# SWReg.net
KiCad netlist of a schematic drawn in Altium Designer
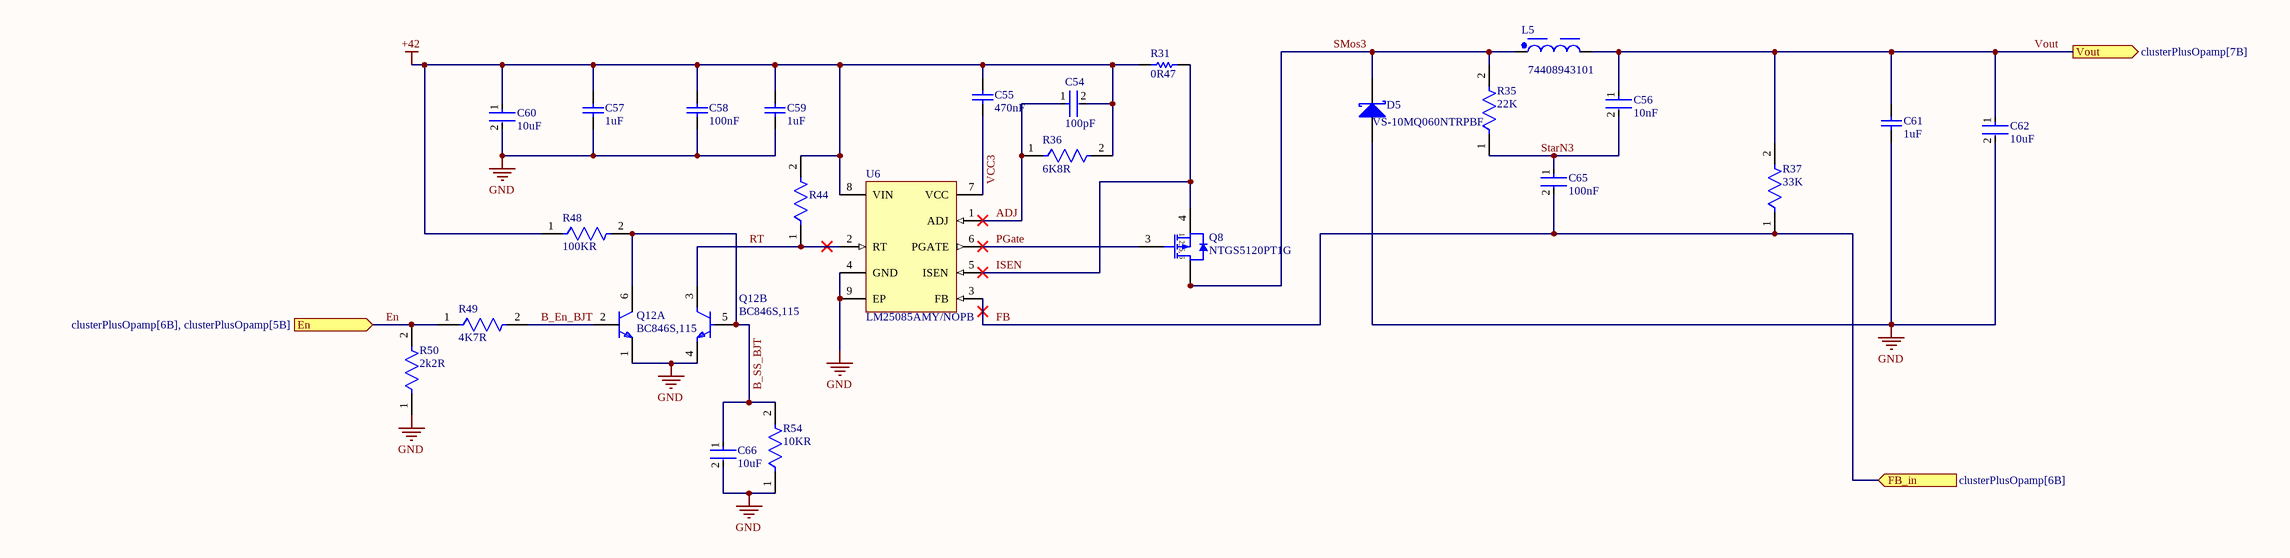
[diagram p0: SWReg.SchDoc]

(export (version "E")
  (design (tool "Eeschema 10.0.6"))
  (components
    (comp (ref "C54")
      (value "100pF")
      (footprint "FP-C0402-BB-MFG")
      (description "CAP CER 10PF 25V 5% NP0 0402")
      (fields
        (field (name "OCTOPART") "https://octopart.com/c0402c100j3gactu-kemet-9138549")
        (field (name "MANUFACTURER PART NUMBER") "C0402C100J3GACTU")
      )
      (libsource (lib "Altium Content Vault") (part "b4654b650e69147ec39a6b967a45e02"))
    )
    (comp (ref "C55")
      (value "470nF")
      (footprint "CAPC1608X90X35LL15T15")
      (fields (field (name "MANUFACTURER") "Kemet") (field (name "PART NUMBER") "C0603C105K4RACTU"))
      (libsource (lib "Altium Content Vault") (part "CAP"))
    )
    (comp (ref "C56")
      (value "10nF")
      (footprint "FP-CC1206-1_25-MFG")
      (description "CAP CER 0.1UF 50V X7R 1206")
      (fields
        (field (name "OCTOPART") "https://octopart.com/cc1206krx7r9bb104-yageo-39467816")
        (field (name "TOLERANCE") "0.1")
      )
      (libsource (lib "Altium Content Vault") (part "11868f565c42a9108669ba33697ecf6"))
    )
    (comp (ref "C57")
      (value "1uF")
      (footprint "CAPC1608X90X35LL15T15")
      (fields (field (name "MANUFACTURER") "Kemet") (field (name "PART NUMBER") "C0603C105K4RACTU"))
      (libsource (lib "Altium Content Vault") (part "CAP"))
    )
    (comp (ref "C58")
      (value "100nF")
      (footprint "CAPC1608X90X35LL15T15")
      (fields (field (name "MANUFACTURER") "Kemet") (field (name "PART NUMBER") "C0603C105K4RACTU"))
      (libsource (lib "Altium Content Vault") (part "CAP"))
    )
    (comp (ref "C59")
      (value "1uF")
      (footprint "CAPC1608X90X35LL15T15")
      (fields (field (name "MANUFACTURER") "Kemet") (field (name "PART NUMBER") "C0603C105K4RACTU"))
      (libsource (lib "Altium Content Vault") (part "CAP"))
    )
    (comp (ref "C60")
      (value "10uF")
      (footprint "FP-CC1206-1_25-MFG")
      (description "CAP CER 0.1UF 50V X7R 1206")
      (fields
        (field (name "OCTOPART") "https://octopart.com/cc1206krx7r9bb104-yageo-39467816")
        (field (name "TOLERANCE") "0.1")
      )
      (libsource (lib "Altium Content Vault") (part "11868f565c42a9108669ba33697ecf6"))
    )
    (comp (ref "C61")
      (value "1uF")
      (footprint "CAPC2013X140X50LL20T25")
      (fields (field (name "PART NUMBER") "C0805C105K3RACTU") (field (name "MANUFACTURER") "Kemet"))
      (libsource (lib "Altium Content Vault") (part "CAP"))
    )
    (comp (ref "C62")
      (value "10uF")
      (footprint "FP-GRM31C-0_2-e0_3_0_8-MFG")
      (description "Chip Multilayer Ceramic Capacitors for General Purpose, 1206, 10uF, X7R, 15%, 10%, 25V")
      (fields (field (name "TOLERANCE") "10%") (field (name "VOLTAGE") "25V"))
      (libsource (lib "Altium Content Vault") (part "02cd4be3c70576c341d710602a673aa"))
    )
    (comp (ref "C65")
      (value "100nF")
      (footprint "FP-CC1206-1_25-MFG")
      (description "CAP CER 0.1UF 50V X7R 1206")
      (fields
        (field (name "OCTOPART") "https://octopart.com/cc1206krx7r9bb104-yageo-39467816")
        (field (name "TOLERANCE") "0.1")
      )
      (libsource (lib "Altium Content Vault") (part "11868f565c42a9108669ba33697ecf6"))
    )
    (comp (ref "C66")
      (value "10uF")
      (footprint "FP-CC1206-1_25-MFG")
      (description "CAP CER 0.1UF 50V X7R 1206")
      (fields
        (field (name "OCTOPART") "https://octopart.com/cc1206krx7r9bb104-yageo-39467816")
        (field (name "TOLERANCE") "0.1")
      )
      (libsource (lib "Altium Content Vault") (part "11868f565c42a9108669ba33697ecf6"))
    )
    (comp (ref "D5")
      (value "VS-10MQ060NTRPBF")
      (footprint "VISH-DO-214AC_V")
      (fields (field (name "MANUFACTURER") "Vishay"))
      (libsource (lib "Altium Content Vault") (part "DSKY-AK-2"))
    )
    (comp (ref "L5")
      (value "74408943101")
      (footprint "WE-SPC_4838")
      (fields (field (name "TOLERANCE") "20%"))
      (libsource (lib "Altium Content Vault") (part "Inductor - 2"))
    )
    (comp (ref "Q8")
      (value "NTGS5120PT1G")
      (footprint "ONSC-TSOP-6-318G-02_V")
      (description "Power MOSFET, -60 V, -2.9 A, Single P-Channel, 6-Pin TSOP, Pb-Free, Tape and Reel")
      (fields (field (name "MANUFACTURER") "On Semiconductor"))
      (libsource (lib "Altium Content Vault") (part "ONSC-PMOS-6_C"))
    )
    (comp (ref "Q12")
      (value "BC846S,115")
      (footprint "FP-SOT363-MFG")
      (description "TRANS 2NPN 65V 0.1A 6TSSOP")
      (fields
        (field (name "MANUFACTURER") "Nexperia")
        (field (name "OCTOPART") "https://octopart.com/bc846s%2C115-nexperia-78739099")
      )
      (libsource (lib "Altium Content Vault") (part "d6cee8eb750607eedcaf46266e24fa2"))
    )
    (comp (ref "R31")
      (value "0R47")
      (footprint "RESC3216X70X50NL05T20")
      (fields (field (name "PART NUMBER") "ERJ8BWFR068V") (field (name "MANUFACTURER") "Panasonic"))
      (libsource (lib "Altium Content Vault") (part "RES"))
    )
    (comp (ref "R35")
      (value "22K")
      (footprint "FP-RC0402-0_4-MFG")
      (fields (field (name "TOLERANCE") "5%"))
      (libsource (lib "Altium Content Vault") (part "RC0402JR-074K7L"))
    )
    (comp (ref "R36")
      (value "6K8R")
      (footprint "FP-RC0402-0_4-MFG")
      (fields (field (name "TOLERANCE") "5%"))
      (libsource (lib "Altium Content Vault") (part "RC0402JR-074K7L"))
    )
    (comp (ref "R37")
      (value "33K")
      (footprint "FP-RC0603-0_55-MFG")
      (description "RES SMD 100K OHM 1% 1/10W 0603")
      (fields (field (name "TOLERANCE") "1%"))
      (libsource (lib "Altium Content Vault") (part "1029c3af85768c4190bb7ad29bc67b5"))
    )
    (comp (ref "R44")
      (value "240K")
      (footprint "FP-CRCW0603-e3-MFG")
      (description "RES Thick Film, 68kΩ, 1%, 0.1W, 100ppm/°C, 0603")
      (fields (field (name "TOLERANCE") "1%"))
      (libsource (lib "Altium Content Vault") (part "1029c3af85768c4190bb7ad29bc67b5"))
    )
    (comp (ref "R48")
      (value "100KR")
      (footprint "FP-RC0402-0_4-MFG")
      (fields (field (name "TOLERANCE") "5%"))
      (libsource (lib "Altium Content Vault") (part "RC0402JR-074K7L"))
    )
    (comp (ref "R49")
      (value "4K7R")
      (footprint "FP-RC0402-0_4-MFG")
      (fields (field (name "TOLERANCE") "5%"))
      (libsource (lib "Altium Content Vault") (part "RC0402JR-074K7L"))
    )
    (comp (ref "R50")
      (value "2k2R")
      (footprint "FP-RC0402-0_4-MFG")
      (fields (field (name "TOLERANCE") "5%"))
      (libsource (lib "Altium Content Vault") (part "RC0402JR-074K7L"))
    )
    (comp (ref "R54")
      (value "10KR")
      (footprint "FP-RC0402-0_4-MFG")
      (fields (field (name "TOLERANCE") "5%"))
      (libsource (lib "Altium Content Vault") (part "RC0402JR-074K7L"))
    )
    (comp (ref "U6")
      (value "LM25085AMY/NOPB")
      (footprint "DGN0008A_M")
      (description "42V Constant On-Time PFET Buck Switching Controller with 0.9V Reference, 8-pin eMSOP, Pb-Free")
      (fields (field (name "MANUFACTURER") "Texas Instruments"))
      (libsource (lib "Altium Content Vault") (part "PM-SWREG-LM25085-IL9"))
    )
  )
  (nets
    (net (code "1") (name "+42") (class "Default")
      (node (ref "C54") (pin "2") (pinfunction "2_2") (pintype "passive"))
      (node (ref "C55") (pin "2") (pinfunction "2_2") (pintype "passive"))
      (node (ref "C57") (pin "2") (pinfunction "2_2") (pintype "passive"))
      (node (ref "C58") (pin "2") (pinfunction "2_2") (pintype "passive"))
      (node (ref "C59") (pin "2") (pinfunction "2_2") (pintype "passive"))
      (node (ref "C60") (pin "1") (pinfunction "1_1") (pintype "passive"))
      (node (ref "R31") (pin "1") (pinfunction "1_1") (pintype "passive"))
      (node (ref "R36") (pin "2") (pinfunction "2_2") (pintype "passive"))
      (node (ref "R44") (pin "2") (pinfunction "2_2") (pintype "passive"))
      (node (ref "R48") (pin "1") (pinfunction "1_1") (pintype "passive"))
      (node (ref "U6") (pin "8") (pinfunction "VIN_8") (pintype "power_in"))
    )
    (net (code "2") (name "/ADJ") (class "Default")
      (node (ref "C54") (pin "1") (pinfunction "1_1") (pintype "passive"))
      (node (ref "R36") (pin "1") (pinfunction "1_1") (pintype "passive"))
      (node (ref "U6") (pin "1") (pinfunction "ADJ_1") (pintype "input"))
    )
    (net (code "3") (name "/B_En_BJT") (class "Default")
      (node (ref "Q12") (pin "2") (pinfunction "B_2") (pintype "passive"))
      (node (ref "R49") (pin "2") (pinfunction "2_2") (pintype "passive"))
    )
    (net (code "4") (name "/B_SS_BJT") (class "Default")
      (node (ref "C66") (pin "1") (pinfunction "1_1") (pintype "passive"))
      (node (ref "Q12") (pin "5") (pinfunction "B_5") (pintype "passive"))
      (node (ref "Q12") (pin "6") (pinfunction "C_6") (pintype "passive"))
      (node (ref "R48") (pin "2") (pinfunction "2_2") (pintype "passive"))
      (node (ref "R54") (pin "2") (pinfunction "2_2") (pintype "passive"))
    )
    (net (code "5") (name "/En") (class "Default")
      (node (ref "R49") (pin "1") (pinfunction "1_1") (pintype "passive"))
      (node (ref "R50") (pin "2") (pinfunction "2_2") (pintype "passive"))
    )
    (net (code "6") (name "/FB") (class "Default")
      (node (ref "C65") (pin "2") (pinfunction "2_2") (pintype "passive"))
      (node (ref "R37") (pin "1") (pinfunction "1_1") (pintype "passive"))
      (node (ref "U6") (pin "3") (pinfunction "FB_3") (pintype "input"))
    )
    (net (code "7") (name "/ISEN") (class "Default")
      (node (ref "Q8") (pin "4") (pinfunction "S_4") (pintype "passive"))
      (node (ref "R31") (pin "2") (pinfunction "2_2") (pintype "passive"))
      (node (ref "U6") (pin "5") (pinfunction "ISEN_5") (pintype "input"))
    )
    (net (code "8") (name "/PGate") (class "Default")
      (node (ref "Q8") (pin "3") (pinfunction "G_3") (pintype "passive"))
      (node (ref "U6") (pin "6") (pinfunction "PGATE_6") (pintype "output"))
    )
    (net (code "9") (name "/RT") (class "Default")
      (node (ref "Q12") (pin "3") (pinfunction "C_3") (pintype "passive"))
      (node (ref "R44") (pin "1") (pinfunction "1_1") (pintype "passive"))
      (node (ref "U6") (pin "2") (pinfunction "RT_2") (pintype "input"))
    )
    (net (code "10") (name "/SMos3") (class "Default")
      (node (ref "D5") (pin "2") (pinfunction "K_2") (pintype "passive"))
      (node (ref "L5") (pin "1") (pinfunction "1_1") (pintype "passive"))
      (node (ref "Q8") (pin "1") (pinfunction "D_1") (pintype "passive"))
      (node (ref "Q8") (pin "2") (pinfunction "D_2") (pintype "passive"))
      (node (ref "Q8") (pin "5") (pinfunction "D_5") (pintype "passive"))
      (node (ref "Q8") (pin "6") (pinfunction "D_6") (pintype "passive"))
      (node (ref "R35") (pin "2") (pinfunction "2_2") (pintype "passive"))
    )
    (net (code "11") (name "/StarN3") (class "Default")
      (node (ref "C56") (pin "2") (pinfunction "2_2") (pintype "passive"))
      (node (ref "C65") (pin "1") (pinfunction "1_1") (pintype "passive"))
      (node (ref "R35") (pin "1") (pinfunction "1_1") (pintype "passive"))
    )
    (net (code "12") (name "/VCC3") (class "Default")
      (node (ref "C55") (pin "1") (pinfunction "1_1") (pintype "passive"))
      (node (ref "U6") (pin "7") (pinfunction "VCC_7") (pintype "power_in"))
    )
    (net (code "13") (name "/Vout") (class "Default")
      (node (ref "C56") (pin "1") (pinfunction "1_1") (pintype "passive"))
      (node (ref "C61") (pin "2") (pinfunction "2_2") (pintype "passive"))
      (node (ref "C62") (pin "1") (pinfunction "1_1") (pintype "passive"))
      (node (ref "L5") (pin "2") (pinfunction "2_2") (pintype "passive"))
      (node (ref "R37") (pin "2") (pinfunction "2_2") (pintype "passive"))
    )
    (net (code "14") (name "GND") (class "Default")
      (node (ref "C57") (pin "1") (pinfunction "1_1") (pintype "passive"))
      (node (ref "C58") (pin "1") (pinfunction "1_1") (pintype "passive"))
      (node (ref "C59") (pin "1") (pinfunction "1_1") (pintype "passive"))
      (node (ref "C60") (pin "2") (pinfunction "2_2") (pintype "passive"))
      (node (ref "C61") (pin "1") (pinfunction "1_1") (pintype "passive"))
      (node (ref "C62") (pin "2") (pinfunction "2_2") (pintype "passive"))
      (node (ref "C66") (pin "2") (pinfunction "2_2") (pintype "passive"))
      (node (ref "D5") (pin "1") (pinfunction "A_1") (pintype "passive"))
      (node (ref "Q12") (pin "1") (pinfunction "E_1") (pintype "passive"))
      (node (ref "Q12") (pin "4") (pinfunction "E_4") (pintype "passive"))
      (node (ref "R50") (pin "1") (pinfunction "1_1") (pintype "passive"))
      (node (ref "R54") (pin "1") (pinfunction "1_1") (pintype "passive"))
      (node (ref "U6") (pin "4") (pinfunction "GND_4") (pintype "power_in"))
      (node (ref "U6") (pin "9") (pinfunction "EP_9") (pintype "power_in"))
    )
  )
)
